# SPITEMP3.net
KiCad netlist of a schematic drawn in Altium Designer
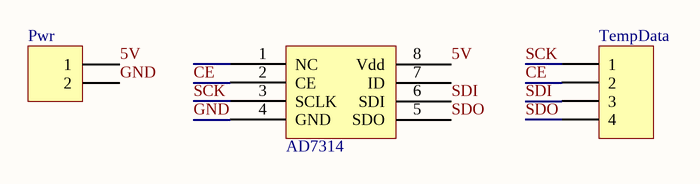
[diagram p0: SPITEMP3.SchDoc]

(export (version "E")
  (design (tool "Eeschema 10.0.6"))
  (components
    (comp (ref "AD7314")
      (value "SPI Temp Sensor")
      (footprint "AD7314")
      (description "SPI Temp Sensor (8-lead MSOP")
      (libsource (lib "AD7314") (part "AD7314"))
    )
    (comp (ref "Pwr")
      (value "~")
      (footprint "HDR1X2")
      (description "Header, 2-Pin")
      (fields (field (name "PUBLISHER") "Altium Limited"))
      (libsource (lib "Miscellaneous Connectors") (part "Header 2"))
    )
    (comp (ref "TempData")
      (value "Header for Temperature Data")
      (footprint "HDR1X4")
      (description "Header, 4-Pin")
      (fields (field (name "PUBLISHER") "Altium Limited"))
      (libsource (lib "Miscellaneous Connectors") (part "Header 4"))
    )
  )
  (nets
    (net (code "1") (name "/5V") (class "Default")
      (node (ref "AD7314") (pin "8") (pinfunction "Vdd_8") (pintype "passive"))
      (node (ref "Pwr") (pin "1") (pinfunction "1_1") (pintype "passive"))
    )
    (net (code "2") (name "/CE") (class "Default")
      (node (ref "AD7314") (pin "2") (pinfunction "CE_2") (pintype "passive"))
      (node (ref "TempData") (pin "2") (pinfunction "2_2") (pintype "passive"))
    )
    (net (code "3") (name "/GND") (class "Default")
      (node (ref "AD7314") (pin "4") (pinfunction "GND_4") (pintype "passive"))
      (node (ref "Pwr") (pin "2") (pinfunction "2_2") (pintype "passive"))
    )
    (net (code "4") (name "/SCK") (class "Default")
      (node (ref "AD7314") (pin "3") (pinfunction "SCLK_3") (pintype "passive"))
      (node (ref "TempData") (pin "1") (pinfunction "1_1") (pintype "passive"))
    )
    (net (code "5") (name "/SDI") (class "Default")
      (node (ref "AD7314") (pin "6") (pinfunction "SDI_6") (pintype "passive"))
      (node (ref "TempData") (pin "3") (pinfunction "3_3") (pintype "passive"))
    )
    (net (code "6") (name "/SDO") (class "Default")
      (node (ref "AD7314") (pin "5") (pinfunction "SDO_5") (pintype "passive"))
      (node (ref "TempData") (pin "4") (pinfunction "4_4") (pintype "passive"))
    )
    (net (code "7") (name "unconnected-(AD7314-ID-Pad7)") (class "Default")
      (node (ref "AD7314") (pin "7") (pinfunction "ID_7") (pintype "passive"))
    )
    (net (code "8") (name "unconnected-(AD7314-NC-Pad1)") (class "Default")
      (node (ref "AD7314") (pin "1") (pinfunction "NC_1") (pintype "passive"))
    )
  )
)
